# RGB_Station_v10.net
KiCad netlist of a schematic drawn in EAGLE
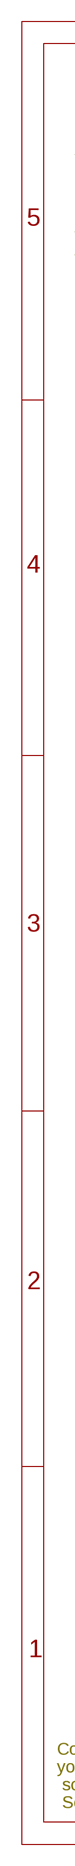
[diagram p0: schematic, sheet 1, part 1 of 2]
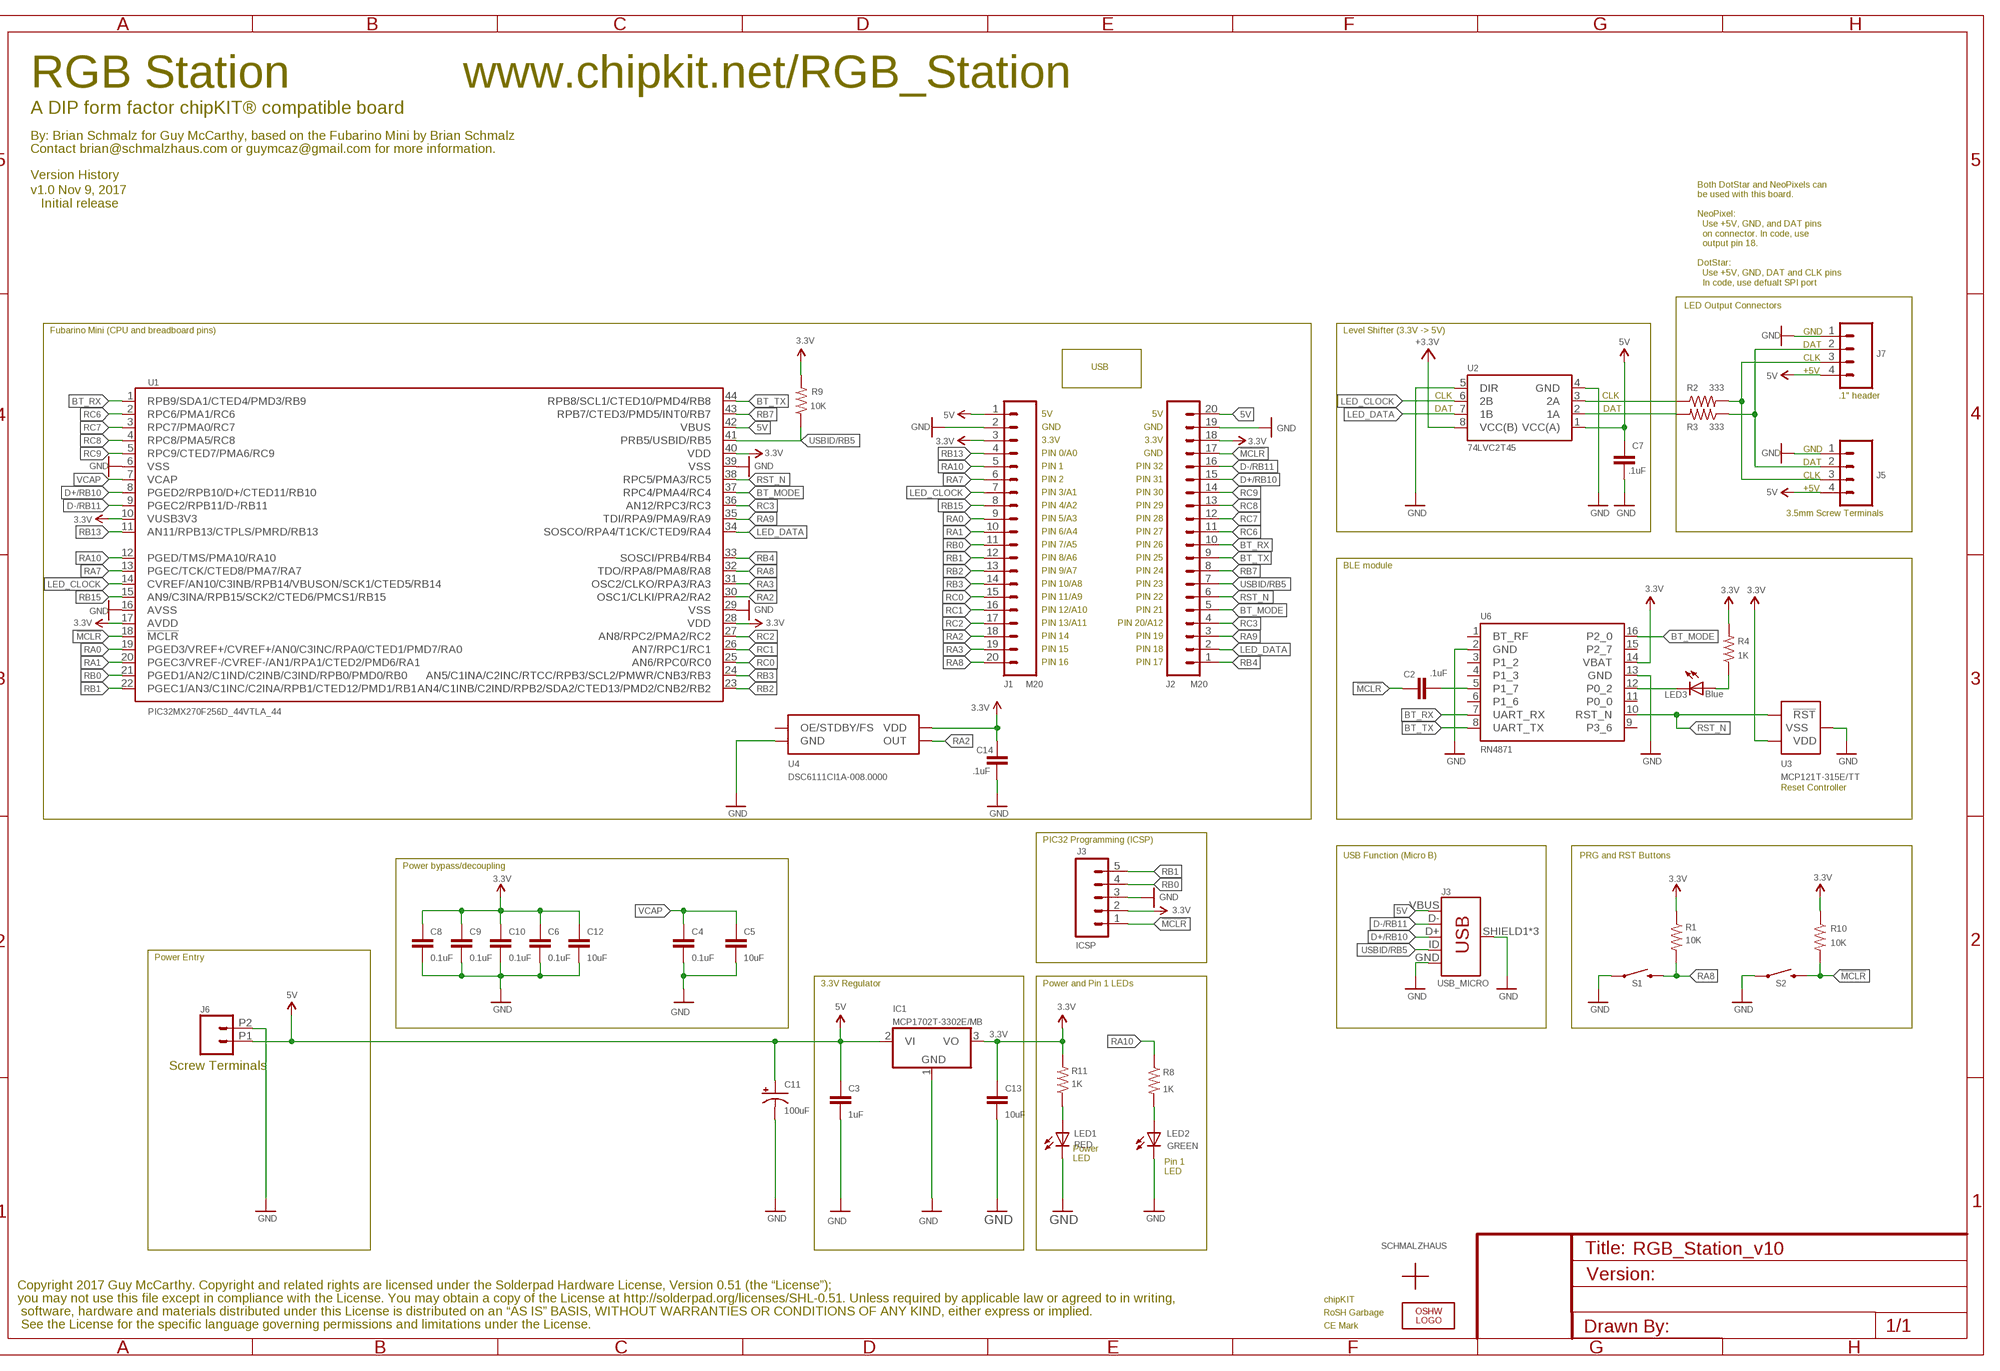
[diagram p1: schematic, sheet 1, part 2 of 2]

(export (version "E")
  (design (tool "Eeschema 10.0.6"))
  (components
    (comp (ref "C2")
      (value ".1uF")
      (footprint "eagle-import:0603-CAP")
      (libsource (lib "eagle-import") (part "SparkFun-Capacitors_CAP0603-CAP"))
    )
    (comp (ref "C3")
      (value "1uF")
      (footprint "eagle-import:0603-CAP")
      (libsource (lib "eagle-import") (part "SparkFun_CAP0603-CAP"))
    )
    (comp (ref "C4")
      (value "0.1uF")
      (footprint "eagle-import:0603-CAP")
      (libsource (lib "eagle-import") (part "SparkFun_CAP0603-CAP"))
    )
    (comp (ref "C5")
      (value "10uF")
      (footprint "eagle-import:0805")
      (libsource (lib "eagle-import") (part "CAP0805"))
    )
    (comp (ref "C6")
      (value "0.1uF")
      (footprint "eagle-import:0603")
      (libsource (lib "eagle-import") (part "CAP0603"))
    )
    (comp (ref "C7")
      (value ".1uF")
      (footprint "eagle-import:0603-CAP")
      (libsource (lib "eagle-import") (part "SparkFun-Capacitors_CAP0603-CAP"))
    )
    (comp (ref "C8")
      (value "0.1uF")
      (footprint "eagle-import:0603-CAP")
      (libsource (lib "eagle-import") (part "SparkFun_CAP0603-CAP"))
    )
    (comp (ref "C9")
      (value "0.1uF")
      (footprint "eagle-import:0603-CAP")
      (libsource (lib "eagle-import") (part "SparkFun_CAP0603-CAP"))
    )
    (comp (ref "C10")
      (value "0.1uF")
      (footprint "eagle-import:0603")
      (libsource (lib "eagle-import") (part "CAP0603"))
    )
    (comp (ref "C11")
      (value "100uF")
      (footprint "eagle-import:PANASONIC_C")
      (libsource (lib "eagle-import") (part "CAP_POLC"))
    )
    (comp (ref "C12")
      (value "10uF")
      (footprint "eagle-import:0805")
      (libsource (lib "eagle-import") (part "CAP0805"))
    )
    (comp (ref "C13")
      (value "10uF")
      (footprint "eagle-import:0805")
      (libsource (lib "eagle-import") (part "SparkFun02-20-08_CAP0805"))
    )
    (comp (ref "C14")
      (value ".1uF")
      (footprint "eagle-import:0603-CAP")
      (libsource (lib "eagle-import") (part "SparkFun_CAP0603-CAP"))
    )
    (comp (ref "IC1")
      (value "MCP1702T-3302E/MB")
      (footprint "eagle-import:SOT89")
      (libsource (lib "eagle-import") (part "MCP1703MB33"))
    )
    (comp (ref "ICSP")
      (value "J3")
      (footprint "eagle-import:1X05_NOSILK")
      (libsource (lib "eagle-import") (part "M05NOSLILK"))
    )
    (comp (ref "J1")
      (value "M20")
      (footprint "eagle-import:1X20_NO_PIN1")
      (libsource (lib "eagle-import") (part "M20"))
    )
    (comp (ref "J2")
      (value "M20")
      (footprint "eagle-import:1X20_NO_PIN1")
      (libsource (lib "eagle-import") (part "M20"))
    )
    (comp (ref "J3")
      (value "USB_MICRO")
      (footprint "eagle-import:USB-B-MICRO-SMD")
      (libsource (lib "eagle-import") (part "USB_MICRO-B_FEMALE-SMT"))
    )
    (comp (ref "J5")
      (value "CONN_04SCREW")
      (footprint "eagle-import:SCREWTERMINAL-3.5MM-4@1")
      (libsource (lib "eagle-import") (part "CONN_04SCREW"))
    )
    (comp (ref "J6")
      (value "CONN_022.54MM_SCREWTERM")
      (footprint "eagle-import:1X02_2.54_SCREWTERM")
      (libsource (lib "eagle-import") (part "CONN_022.54MM_SCREWTERM"))
    )
    (comp (ref "J7")
      (value "M04PTH")
      (footprint "eagle-import:1X04")
      (libsource (lib "eagle-import") (part "M04PTH"))
    )
    (comp (ref "LED1")
      (value "RED")
      (footprint "eagle-import:LED-0603")
      (libsource (lib "eagle-import") (part "LED0603"))
    )
    (comp (ref "LED2")
      (value "GREEN")
      (footprint "eagle-import:LED-0603")
      (libsource (lib "eagle-import") (part "LED0603"))
    )
    (comp (ref "LED3")
      (value "Blue")
      (footprint "eagle-import:LED-0603")
      (libsource (lib "eagle-import") (part "LED0603"))
    )
    (comp (ref "LOGO1")
      (value "OSHW_LOGO_8MILX0070-NT")
      (footprint "eagle-import:OSHW_8X70_NOTEXT")
      (libsource (lib "eagle-import") (part "OSHW_LOGO_8MILX0070-NT"))
    )
    (comp (ref "R1")
      (value "10K")
      (footprint "eagle-import:0603-RES")
      (libsource (lib "eagle-import") (part "RESISTOR0603-RES"))
    )
    (comp (ref "R2")
      (value "333")
      (footprint "eagle-import:0603-RES")
      (libsource (lib "eagle-import") (part "RESISTOR0603"))
    )
    (comp (ref "R3")
      (value "333")
      (footprint "eagle-import:0603-RES")
      (libsource (lib "eagle-import") (part "RESISTOR0603"))
    )
    (comp (ref "R4")
      (value "1K")
      (footprint "eagle-import:0603-RES")
      (libsource (lib "eagle-import") (part "RESISTOR0603-RES"))
    )
    (comp (ref "R8")
      (value "1K")
      (footprint "eagle-import:0603-RES")
      (libsource (lib "eagle-import") (part "RESISTOR0603-RES"))
    )
    (comp (ref "R9")
      (value "10K")
      (footprint "eagle-import:0603-RES")
      (libsource (lib "eagle-import") (part "RESISTOR0603-RES"))
    )
    (comp (ref "R10")
      (value "10K")
      (footprint "eagle-import:0603-RES")
      (libsource (lib "eagle-import") (part "RESISTOR0603-RES"))
    )
    (comp (ref "R11")
      (value "1K")
      (footprint "eagle-import:0603-RES")
      (libsource (lib "eagle-import") (part "RESISTOR0603-RES"))
    )
    (comp (ref "S1")
      (value "SWITCH-MOMENTARY-SPSTSMD-3")
      (footprint "eagle-import:TACTILE_SWITCH_SMD-3")
      (libsource (lib "eagle-import") (part "SWITCH-MOMENTARY-SPSTSMD-3"))
    )
    (comp (ref "S2")
      (value "SWITCH-MOMENTARY-SPSTSMD-3")
      (footprint "eagle-import:TACTILE_SWITCH_SMD-3")
      (libsource (lib "eagle-import") (part "SWITCH-MOMENTARY-SPSTSMD-3"))
    )
    (comp (ref "U$2")
      (value "CE_MARK5MM")
      (footprint "eagle-import:CE_5MM")
      (libsource (lib "eagle-import") (part "CE_MARK5MM"))
    )
    (comp (ref "U$3")
      (value "ROSH_GARBAGE")
      (footprint "eagle-import:ROHS_GARBAGE_5MM")
      (libsource (lib "eagle-import") (part "ROSH_GARBAGE"))
    )
    (comp (ref "U$4")
      (value "CHIPKIT2MM")
      (footprint "eagle-import:CHIPKIT_2MM")
      (libsource (lib "eagle-import") (part "CHIPKIT2MM"))
    )
    (comp (ref "U$5")
      (value "SCHMALZHAUSSCHMALZHAUS_SMALL")
      (footprint "eagle-import:SCHMALZHAUS_SMALL")
      (libsource (lib "eagle-import") (part "SCHMALZHAUSSCHMALZHAUS_SMALL"))
    )
    (comp (ref "U1")
      (value "PIC32MX270F256D_44VTLA_44")
      (footprint "eagle-import:QFN-44-8X8-NOPAD")
      (libsource (lib "eagle-import") (part "PIC32MX2XX_44QFN44"))
    )
    (comp (ref "U2")
      (value "74LVC2T45")
      (footprint "eagle-import:VSSOP8")
      (libsource (lib "eagle-import") (part "74LVC2T45"))
    )
    (comp (ref "U3")
      (value "MCP121T-315E/TT")
      (footprint "eagle-import:SC70")
      (libsource (lib "eagle-import") (part "MCP1X2_RESET_CONTROLLER"))
    )
    (comp (ref "U4")
      (value "DSC6111CI1A-008.0000")
      (footprint "eagle-import:CDFN-4_3.2X2.5")
      (libsource (lib "eagle-import") (part "DSC61XX"))
    )
    (comp (ref "U6")
      (value "RN4871")
      (footprint "eagle-import:RN4871")
      (libsource (lib "eagle-import") (part "RN4871"))
    )
  )
  (nets
    (net (code "1") (name "+3.3V") (class "Default")
      (node (ref "C10") (pin "1") (pinfunction "1_1") (pintype "passive"))
      (node (ref "C12") (pin "1") (pinfunction "1_1") (pintype "passive"))
      (node (ref "C13") (pin "1") (pinfunction "1_1") (pintype "passive"))
      (node (ref "C14") (pin "2") (pinfunction "2_2") (pintype "passive"))
      (node (ref "C6") (pin "1") (pinfunction "1_1") (pintype "passive"))
      (node (ref "C8") (pin "1") (pinfunction "1_1") (pintype "passive"))
      (node (ref "C9") (pin "1") (pinfunction "1_1") (pintype "passive"))
      (node (ref "IC1") (pin "3") (pinfunction "VO_3") (pintype "passive"))
      (node (ref "ICSP") (pin "2") (pinfunction "2_2") (pintype "passive"))
      (node (ref "J1") (pin "3") (pinfunction "3_3") (pintype "passive"))
      (node (ref "J2") (pin "18") (pinfunction "18_18") (pintype "passive"))
      (node (ref "R1") (pin "1") (pinfunction "1_1") (pintype "passive"))
      (node (ref "R10") (pin "1") (pinfunction "1_1") (pintype "passive"))
      (node (ref "R11") (pin "2") (pinfunction "2_2") (pintype "passive"))
      (node (ref "R4") (pin "2") (pinfunction "2_2") (pintype "passive"))
      (node (ref "R9") (pin "2") (pinfunction "2_2") (pintype "passive"))
      (node (ref "U1") (pin "10") (pinfunction "VUSB3V3_10") (pintype "bidirectional"))
      (node (ref "U1") (pin "17") (pinfunction "AVDD_17") (pintype "bidirectional"))
      (node (ref "U1") (pin "28") (pinfunction "VDD_28") (pintype "bidirectional"))
      (node (ref "U1") (pin "40") (pinfunction "VDD_40") (pintype "bidirectional"))
      (node (ref "U2") (pin "8") (pinfunction "VCC(B)_8") (pintype "bidirectional"))
      (node (ref "U3") (pin "P2") (pinfunction "VDD_P2") (pintype "bidirectional"))
      (node (ref "U4") (pin "P4") (pinfunction "VDD_P4") (pintype "bidirectional"))
      (node (ref "U6") (pin "14") (pinfunction "VBAT_14") (pintype "bidirectional"))
    )
    (net (code "2") (name "/~{MCLR}") (class "Default")
      (node (ref "C2") (pin "2") (pinfunction "2_2") (pintype "passive"))
      (node (ref "ICSP") (pin "1") (pinfunction "1_1") (pintype "passive"))
      (node (ref "J2") (pin "17") (pinfunction "17_17") (pintype "passive"))
      (node (ref "R10") (pin "2") (pinfunction "2_2") (pintype "passive"))
      (node (ref "S2") (pin "4") (pinfunction "2_4") (pintype "passive"))
      (node (ref "U1") (pin "18") (pinfunction "~{MCLR}_18") (pintype "bidirectional"))
    )
    (net (code "3") (name "5V") (class "Default")
      (node (ref "C11") (pin "+") (pinfunction "+_+") (pintype "passive"))
      (node (ref "C3") (pin "1") (pinfunction "1_1") (pintype "passive"))
      (node (ref "C7") (pin "2") (pinfunction "2_2") (pintype "passive"))
      (node (ref "IC1") (pin "2") (pinfunction "VI_2") (pintype "input"))
      (node (ref "IC1") (pin "2@1") (pinfunction "VI1_2@1") (pintype "input"))
      (node (ref "J1") (pin "1") (pinfunction "1_1") (pintype "passive"))
      (node (ref "J2") (pin "20") (pinfunction "20_20") (pintype "passive"))
      (node (ref "J3") (pin "VBUS") (pinfunction "VBUS_VBUS") (pintype "power_in"))
      (node (ref "J5") (pin "4") (pinfunction "4_4") (pintype "passive"))
      (node (ref "J6") (pin "P1") (pinfunction "1_P1") (pintype "passive"))
      (node (ref "J7") (pin "4") (pinfunction "4_4") (pintype "passive"))
      (node (ref "U1") (pin "42") (pinfunction "VBUS_42") (pintype "bidirectional"))
      (node (ref "U2") (pin "1") (pinfunction "VCC(A)_1") (pintype "bidirectional"))
    )
    (net (code "4") (name "BT_MODE") (class "Default")
      (node (ref "J2") (pin "5") (pinfunction "5_5") (pintype "passive"))
      (node (ref "U1") (pin "37") (pinfunction "RPC4/PMA4/RC4_37") (pintype "bidirectional"))
      (node (ref "U6") (pin "16") (pinfunction "P2_0_16") (pintype "bidirectional"))
    )
    (net (code "5") (name "BT_RX") (class "Default")
      (node (ref "J2") (pin "10") (pinfunction "10_10") (pintype "passive"))
      (node (ref "U1") (pin "1") (pinfunction "RPB9/SDA1/CTED4/PMD3/RB9_1") (pintype "bidirectional"))
      (node (ref "U6") (pin "7") (pinfunction "UART_RX_7") (pintype "bidirectional"))
    )
    (net (code "6") (name "BT_TX") (class "Default")
      (node (ref "J2") (pin "9") (pinfunction "9_9") (pintype "passive"))
      (node (ref "U1") (pin "44") (pinfunction "RPB8/SCL1/CTED10/PMD4/RB8_44") (pintype "bidirectional"))
      (node (ref "U6") (pin "8") (pinfunction "UART_TX_8") (pintype "bidirectional"))
    )
    (net (code "7") (name "D+{slash}RB10") (class "Default")
      (node (ref "J2") (pin "15") (pinfunction "15_15") (pintype "passive"))
      (node (ref "J3") (pin "D+") (pinfunction "D+_D+") (pintype "bidirectional"))
      (node (ref "U1") (pin "8") (pinfunction "PGED2/RPB10/D+/CTED11/RB10_8") (pintype "bidirectional"))
    )
    (net (code "8") (name "D-{slash}RB11") (class "Default")
      (node (ref "J2") (pin "16") (pinfunction "16_16") (pintype "passive"))
      (node (ref "J3") (pin "D-") (pinfunction "D-_D-") (pintype "bidirectional"))
      (node (ref "U1") (pin "9") (pinfunction "PGEC2/RPB11/D-/RB11_9") (pintype "bidirectional"))
    )
    (net (code "9") (name "GND") (class "Default")
      (node (ref "C10") (pin "2") (pinfunction "2_2") (pintype "passive"))
      (node (ref "C11") (pin "-") (pinfunction "-_-") (pintype "passive"))
      (node (ref "C12") (pin "2") (pinfunction "2_2") (pintype "passive"))
      (node (ref "C13") (pin "2") (pinfunction "2_2") (pintype "passive"))
      (node (ref "C14") (pin "1") (pinfunction "1_1") (pintype "passive"))
      (node (ref "C3") (pin "2") (pinfunction "2_2") (pintype "passive"))
      (node (ref "C4") (pin "2") (pinfunction "2_2") (pintype "passive"))
      (node (ref "C5") (pin "2") (pinfunction "2_2") (pintype "passive"))
      (node (ref "C6") (pin "2") (pinfunction "2_2") (pintype "passive"))
      (node (ref "C7") (pin "1") (pinfunction "1_1") (pintype "passive"))
      (node (ref "C8") (pin "2") (pinfunction "2_2") (pintype "passive"))
      (node (ref "C9") (pin "2") (pinfunction "2_2") (pintype "passive"))
      (node (ref "IC1") (pin "1") (pinfunction "GND_1") (pintype "passive"))
      (node (ref "ICSP") (pin "3") (pinfunction "3_3") (pintype "passive"))
      (node (ref "J1") (pin "2") (pinfunction "2_2") (pintype "passive"))
      (node (ref "J2") (pin "19") (pinfunction "19_19") (pintype "passive"))
      (node (ref "J3") (pin "GND") (pinfunction "GND_GND") (pintype "power_in"))
      (node (ref "J3") (pin "SHIELD1") (pinfunction "SHIELD_SHIELD1") (pintype "bidirectional"))
      (node (ref "J3") (pin "SHIELD2") (pinfunction "SHIELD_SHIELD2") (pintype "bidirectional"))
      (node (ref "J3") (pin "SHIELD3") (pinfunction "SHIELD_SHIELD3") (pintype "bidirectional"))
      (node (ref "J5") (pin "1") (pinfunction "1_1") (pintype "passive"))
      (node (ref "J6") (pin "P2") (pinfunction "2_P2") (pintype "passive"))
      (node (ref "J7") (pin "1") (pinfunction "1_1") (pintype "passive"))
      (node (ref "LED1") (pin "C") (pinfunction "C_C") (pintype "passive"))
      (node (ref "LED2") (pin "C") (pinfunction "C_C") (pintype "passive"))
      (node (ref "S1") (pin "1") (pinfunction "1_1") (pintype "passive"))
      (node (ref "S2") (pin "1") (pinfunction "1_1") (pintype "passive"))
      (node (ref "U1") (pin "16") (pinfunction "AVSS_16") (pintype "bidirectional"))
      (node (ref "U1") (pin "29") (pinfunction "VSS_29") (pintype "bidirectional"))
      (node (ref "U1") (pin "39") (pinfunction "VSS_39") (pintype "bidirectional"))
      (node (ref "U1") (pin "6") (pinfunction "VSS_6") (pintype "bidirectional"))
      (node (ref "U2") (pin "4") (pinfunction "GND_4") (pintype "bidirectional"))
      (node (ref "U2") (pin "5") (pinfunction "DIR_5") (pintype "bidirectional"))
      (node (ref "U3") (pin "P3") (pinfunction "VSS_P3") (pintype "bidirectional"))
      (node (ref "U4") (pin "P2") (pinfunction "GND_P2") (pintype "bidirectional"))
      (node (ref "U6") (pin "13") (pinfunction "GND_13") (pintype "bidirectional"))
      (node (ref "U6") (pin "2") (pinfunction "GND_2") (pintype "bidirectional"))
    )
    (net (code "10") (name "LED_CLOCK") (class "Default")
      (node (ref "J1") (pin "7") (pinfunction "7_7") (pintype "passive"))
      (node (ref "U1") (pin "14") (pinfunction "CVREF/AN10/C3INB/RPB14/VBUSON/SCK1/CTED5/RB14_14") (pintype "bidirectional"))
      (node (ref "U2") (pin "6") (pinfunction "2B_6") (pintype "bidirectional"))
    )
    (net (code "11") (name "LED_DATA") (class "Default")
      (node (ref "J2") (pin "2") (pinfunction "2_2") (pintype "passive"))
      (node (ref "U1") (pin "34") (pinfunction "SOSCO/RPA4/T1CK/CTED9/RA4_34") (pintype "bidirectional"))
      (node (ref "U2") (pin "7") (pinfunction "1B_7") (pintype "bidirectional"))
    )
    (net (code "12") (name "Net-(J5-Pad2)") (class "Default")
      (node (ref "J5") (pin "2") (pinfunction "2_2") (pintype "passive"))
      (node (ref "J7") (pin "2") (pinfunction "2_2") (pintype "passive"))
      (node (ref "R3") (pin "1") (pinfunction "1_1") (pintype "passive"))
    )
    (net (code "13") (name "Net-(J5-Pad3)") (class "Default")
      (node (ref "J5") (pin "3") (pinfunction "3_3") (pintype "passive"))
      (node (ref "J7") (pin "3") (pinfunction "3_3") (pintype "passive"))
      (node (ref "R2") (pin "2") (pinfunction "2_2") (pintype "passive"))
    )
    (net (code "14") (name "Net-(LED1-PadA)") (class "Default")
      (node (ref "LED1") (pin "A") (pinfunction "A_A") (pintype "passive"))
      (node (ref "R11") (pin "1") (pinfunction "1_1") (pintype "passive"))
    )
    (net (code "15") (name "Net-(LED2-PadA)") (class "Default")
      (node (ref "LED2") (pin "A") (pinfunction "A_A") (pintype "passive"))
      (node (ref "R8") (pin "2") (pinfunction "2_2") (pintype "passive"))
    )
    (net (code "16") (name "Net-(LED3-PadA)") (class "Default")
      (node (ref "LED3") (pin "A") (pinfunction "A_A") (pintype "passive"))
      (node (ref "R4") (pin "1") (pinfunction "1_1") (pintype "passive"))
    )
    (net (code "17") (name "Net-(U2-1A)") (class "Default")
      (node (ref "R3") (pin "2") (pinfunction "2_2") (pintype "passive"))
      (node (ref "U2") (pin "2") (pinfunction "1A_2") (pintype "bidirectional"))
    )
    (net (code "18") (name "Net-(U2-2A)") (class "Default")
      (node (ref "R2") (pin "1") (pinfunction "1_1") (pintype "passive"))
      (node (ref "U2") (pin "3") (pinfunction "2A_3") (pintype "bidirectional"))
    )
    (net (code "19") (name "Net-(U6-P0_2)") (class "Default")
      (node (ref "LED3") (pin "C") (pinfunction "C_C") (pintype "passive"))
      (node (ref "U6") (pin "12") (pinfunction "P0_2_12") (pintype "bidirectional"))
    )
    (net (code "20") (name "Net-(U6-P1_7)") (class "Default")
      (node (ref "C2") (pin "1") (pinfunction "1_1") (pintype "passive"))
      (node (ref "U6") (pin "5") (pinfunction "P1_7_5") (pintype "bidirectional"))
    )
    (net (code "21") (name "RA0") (class "Default")
      (node (ref "J1") (pin "9") (pinfunction "9_9") (pintype "passive"))
      (node (ref "U1") (pin "19") (pinfunction "PGED3/VREF+/CVREF+/AN0/C3INC/RPA0/CTED1/PMD7/RA0_19") (pintype "bidirectional"))
    )
    (net (code "22") (name "RA1") (class "Default")
      (node (ref "J1") (pin "10") (pinfunction "10_10") (pintype "passive"))
      (node (ref "U1") (pin "20") (pinfunction "PGEC3/VREF-/CVREF-/AN1/RPA1/CTED2/PMD6/RA1_20") (pintype "bidirectional"))
    )
    (net (code "23") (name "RA2") (class "Default")
      (node (ref "J1") (pin "18") (pinfunction "18_18") (pintype "passive"))
      (node (ref "U1") (pin "30") (pinfunction "OSC1/CLKI/PRA2/RA2_30") (pintype "bidirectional"))
      (node (ref "U4") (pin "P3") (pinfunction "OUT_P3") (pintype "bidirectional"))
    )
    (net (code "24") (name "RA3") (class "Default")
      (node (ref "J1") (pin "19") (pinfunction "19_19") (pintype "passive"))
      (node (ref "U1") (pin "31") (pinfunction "OSC2/CLKO/RPA3/RA3_31") (pintype "bidirectional"))
    )
    (net (code "25") (name "RA7") (class "Default")
      (node (ref "J1") (pin "6") (pinfunction "6_6") (pintype "passive"))
      (node (ref "U1") (pin "13") (pinfunction "PGEC/TCK/CTED8/PMA7/RA7_13") (pintype "bidirectional"))
    )
    (net (code "26") (name "RA8") (class "Default")
      (node (ref "J1") (pin "20") (pinfunction "20_20") (pintype "passive"))
      (node (ref "R1") (pin "2") (pinfunction "2_2") (pintype "passive"))
      (node (ref "S1") (pin "4") (pinfunction "2_4") (pintype "passive"))
      (node (ref "U1") (pin "32") (pinfunction "TDO/RPA8/PMA8/RA8_32") (pintype "bidirectional"))
    )
    (net (code "27") (name "RA9") (class "Default")
      (node (ref "J2") (pin "3") (pinfunction "3_3") (pintype "passive"))
      (node (ref "U1") (pin "35") (pinfunction "TDI/RPA9/PMA9/RA9_35") (pintype "bidirectional"))
    )
    (net (code "28") (name "RA10") (class "Default")
      (node (ref "J1") (pin "5") (pinfunction "5_5") (pintype "passive"))
      (node (ref "R8") (pin "1") (pinfunction "1_1") (pintype "passive"))
      (node (ref "U1") (pin "12") (pinfunction "PGED/TMS/PMA10/RA10_12") (pintype "bidirectional"))
    )
    (net (code "29") (name "RB0") (class "Default")
      (node (ref "ICSP") (pin "4") (pinfunction "4_4") (pintype "passive"))
      (node (ref "J1") (pin "11") (pinfunction "11_11") (pintype "passive"))
      (node (ref "U1") (pin "21") (pinfunction "PGED1/AN2/C1IND/C2INB/C3IND/RPB0/PMD0/RB0_21") (pintype "bidirectional"))
    )
    (net (code "30") (name "RB1") (class "Default")
      (node (ref "ICSP") (pin "5") (pinfunction "5_5") (pintype "passive"))
      (node (ref "J1") (pin "12") (pinfunction "12_12") (pintype "passive"))
      (node (ref "U1") (pin "22") (pinfunction "PGEC1/AN3/C1INC/C2INA/RPB1/CTED12/PMD1/RB1_22") (pintype "bidirectional"))
    )
    (net (code "31") (name "RB2") (class "Default")
      (node (ref "J1") (pin "13") (pinfunction "13_13") (pintype "passive"))
      (node (ref "U1") (pin "23") (pinfunction "AN4/C1INB/C2IND/RPB2/SDA2/CTED13/PMD2/CNB2/RB2_23") (pintype "bidirectional"))
    )
    (net (code "32") (name "RB3") (class "Default")
      (node (ref "J1") (pin "14") (pinfunction "14_14") (pintype "passive"))
      (node (ref "U1") (pin "24") (pinfunction "AN5/C1INA/C2INC/RTCC/RPB3/SCL2/PMWR/CNB3/RB3_24") (pintype "bidirectional"))
    )
    (net (code "33") (name "RB4") (class "Default")
      (node (ref "J2") (pin "1") (pinfunction "1_1") (pintype "passive"))
      (node (ref "U1") (pin "33") (pinfunction "SOSCI/PRB4/RB4_33") (pintype "bidirectional"))
    )
    (net (code "34") (name "RB7") (class "Default")
      (node (ref "J2") (pin "8") (pinfunction "8_8") (pintype "passive"))
      (node (ref "U1") (pin "43") (pinfunction "RPB7/CTED3/PMD5/INT0/RB7_43") (pintype "bidirectional"))
    )
    (net (code "35") (name "RB13") (class "Default")
      (node (ref "J1") (pin "4") (pinfunction "4_4") (pintype "passive"))
      (node (ref "U1") (pin "11") (pinfunction "AN11/RPB13/CTPLS/PMRD/RB13_11") (pintype "bidirectional"))
    )
    (net (code "36") (name "RB15") (class "Default")
      (node (ref "J1") (pin "8") (pinfunction "8_8") (pintype "passive"))
      (node (ref "U1") (pin "15") (pinfunction "AN9/C3INA/RPB15/SCK2/CTED6/PMCS1/RB15_15") (pintype "bidirectional"))
    )
    (net (code "37") (name "RC0") (class "Default")
      (node (ref "J1") (pin "15") (pinfunction "15_15") (pintype "passive"))
      (node (ref "U1") (pin "25") (pinfunction "AN6/RPC0/RC0_25") (pintype "bidirectional"))
    )
    (net (code "38") (name "RC1") (class "Default")
      (node (ref "J1") (pin "16") (pinfunction "16_16") (pintype "passive"))
      (node (ref "U1") (pin "26") (pinfunction "AN7/RPC1/RC1_26") (pintype "bidirectional"))
    )
    (net (code "39") (name "RC2") (class "Default")
      (node (ref "J1") (pin "17") (pinfunction "17_17") (pintype "passive"))
      (node (ref "U1") (pin "27") (pinfunction "AN8/RPC2/PMA2/RC2_27") (pintype "bidirectional"))
    )
    (net (code "40") (name "RC3") (class "Default")
      (node (ref "J2") (pin "4") (pinfunction "4_4") (pintype "passive"))
      (node (ref "U1") (pin "36") (pinfunction "AN12/RPC3/RC3_36") (pintype "bidirectional"))
    )
    (net (code "41") (name "RC6") (class "Default")
      (node (ref "J2") (pin "11") (pinfunction "11_11") (pintype "passive"))
      (node (ref "U1") (pin "2") (pinfunction "RPC6/PMA1/RC6_2") (pintype "bidirectional"))
    )
    (net (code "42") (name "RC7") (class "Default")
      (node (ref "J2") (pin "12") (pinfunction "12_12") (pintype "passive"))
      (node (ref "U1") (pin "3") (pinfunction "RPC7/PMA0/RC7_3") (pintype "bidirectional"))
    )
    (net (code "43") (name "RC8") (class "Default")
      (node (ref "J2") (pin "13") (pinfunction "13_13") (pintype "passive"))
      (node (ref "U1") (pin "4") (pinfunction "RPC8/PMA5/RC8_4") (pintype "bidirectional"))
    )
    (net (code "44") (name "RC9") (class "Default")
      (node (ref "J2") (pin "14") (pinfunction "14_14") (pintype "passive"))
      (node (ref "U1") (pin "5") (pinfunction "RPC9/CTED7/PMA6/RC9_5") (pintype "bidirectional"))
    )
    (net (code "45") (name "RST_N") (class "Default")
      (node (ref "J2") (pin "6") (pinfunction "6_6") (pintype "passive"))
      (node (ref "U1") (pin "38") (pinfunction "RPC5/PMA3/RC5_38") (pintype "bidirectional"))
      (node (ref "U3") (pin "P1") (pinfunction "~{RST}_P1") (pintype "bidirectional"))
      (node (ref "U6") (pin "10") (pinfunction "RST_N_10") (pintype "bidirectional"))
    )
    (net (code "46") (name "USBID{slash}RB5") (class "Default")
      (node (ref "J2") (pin "7") (pinfunction "7_7") (pintype "passive"))
      (node (ref "J3") (pin "ID") (pinfunction "ID_ID") (pintype "bidirectional"))
      (node (ref "R9") (pin "1") (pinfunction "1_1") (pintype "passive"))
      (node (ref "U1") (pin "41") (pinfunction "PRB5/USBID/RB5_41") (pintype "bidirectional"))
    )
    (net (code "47") (name "VCAP") (class "Default")
      (node (ref "C4") (pin "1") (pinfunction "1_1") (pintype "passive"))
      (node (ref "C5") (pin "1") (pinfunction "1_1") (pintype "passive"))
      (node (ref "U1") (pin "7") (pinfunction "VCAP_7") (pintype "bidirectional"))
    )
    (net (code "48") (name "unconnected-(U4-OE{slash}STDBY{slash}FS-PadP1)") (class "Default")
      (node (ref "U4") (pin "P1") (pinfunction "OE/STDBY/FS_P1") (pintype "bidirectional"))
    )
    (net (code "49") (name "unconnected-(U6-BT_RF-Pad1)") (class "Default")
      (node (ref "U6") (pin "1") (pinfunction "BT_RF_1") (pintype "bidirectional"))
    )
    (net (code "50") (name "unconnected-(U6-P0_0-Pad11)") (class "Default")
      (node (ref "U6") (pin "11") (pinfunction "P0_0_11") (pintype "bidirectional"))
    )
    (net (code "51") (name "unconnected-(U6-P1_2-Pad3)") (class "Default")
      (node (ref "U6") (pin "3") (pinfunction "P1_2_3") (pintype "bidirectional"))
    )
    (net (code "52") (name "unconnected-(U6-P1_3-Pad4)") (class "Default")
      (node (ref "U6") (pin "4") (pinfunction "P1_3_4") (pintype "bidirectional"))
    )
    (net (code "53") (name "unconnected-(U6-P1_6-Pad6)") (class "Default")
      (node (ref "U6") (pin "6") (pinfunction "P1_6_6") (pintype "bidirectional"))
    )
    (net (code "54") (name "unconnected-(U6-P2_7-Pad15)") (class "Default")
      (node (ref "U6") (pin "15") (pinfunction "P2_7_15") (pintype "bidirectional"))
    )
    (net (code "55") (name "unconnected-(U6-P3_6-Pad9)") (class "Default")
      (node (ref "U6") (pin "9") (pinfunction "P3_6_9") (pintype "bidirectional"))
    )
  )
)
